# BOTTOM_BRD_v_1_0_3.net
KiCad netlist of a schematic drawn in EAGLE
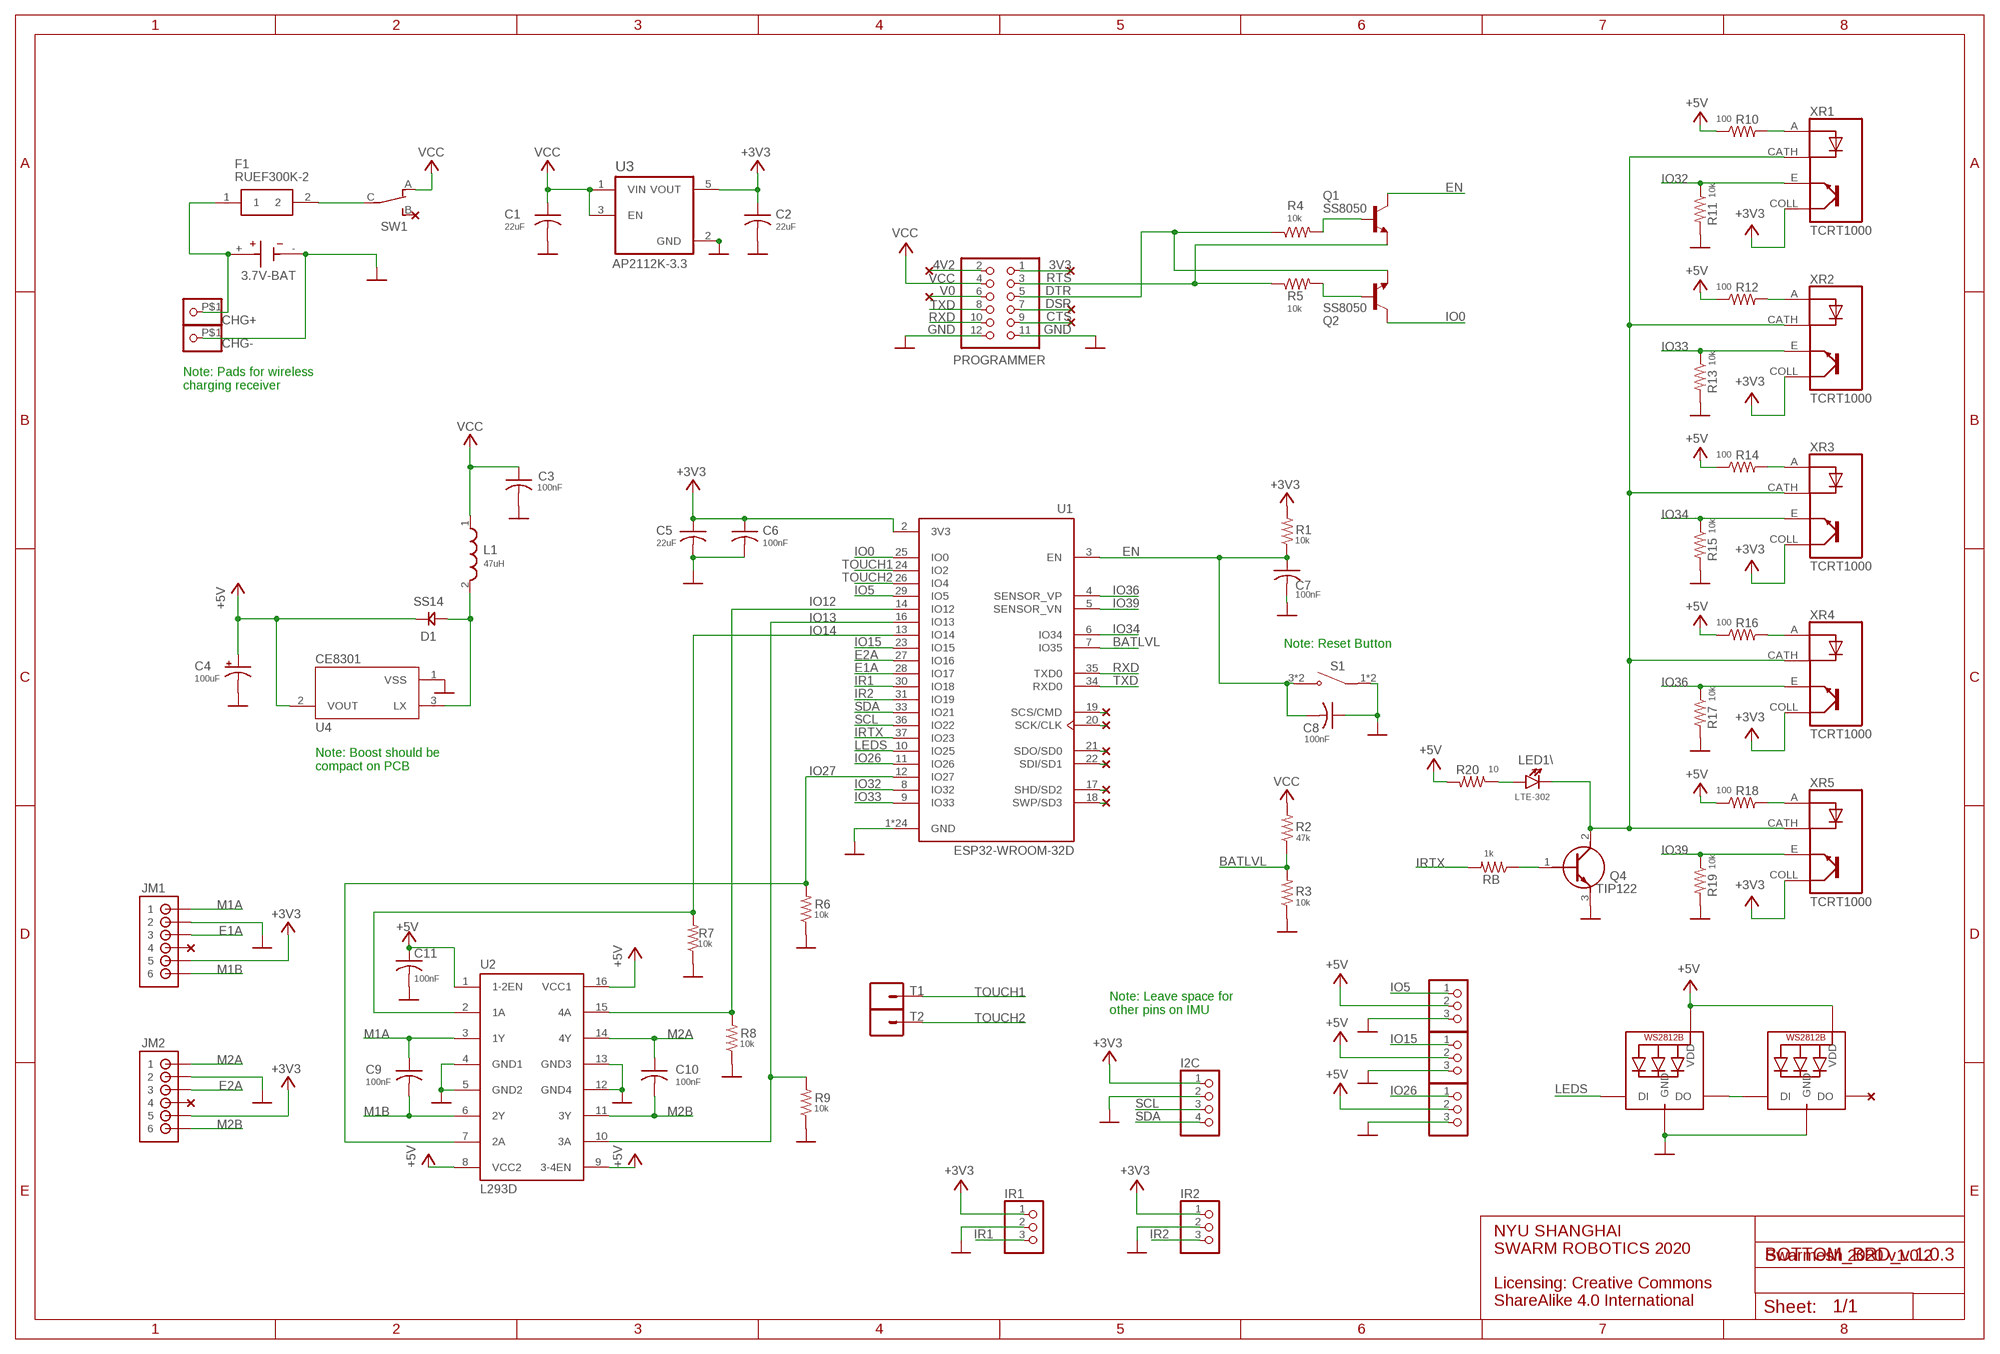
[diagram p0: schematic, sheet 1]

(export (version "E")
  (design (tool "Eeschema 10.0.6"))
  (components
    (comp (ref "BT")
      (value "3.7V-BAT")
      (footprint "eagle-import:BAT_6S-AA")
      (fields (field (name "MF") "MPD") (field (name "MP") "6S-AA"))
      (libsource (lib "eagle-import") (part "6S-AA"))
    )
    (comp (ref "C1")
      (value "22uF")
      (footprint "eagle-import:C0805")
      (libsource (lib "eagle-import") (part "C-USC0805"))
    )
    (comp (ref "C2")
      (value "22uF")
      (footprint "eagle-import:C0805")
      (libsource (lib "eagle-import") (part "C-USC0805"))
    )
    (comp (ref "C3")
      (value "100nF")
      (footprint "eagle-import:C0805")
      (libsource (lib "eagle-import") (part "C-USC0805"))
    )
    (comp (ref "C4")
      (value "100uF")
      (footprint "eagle-import:153CLV-0605")
      (libsource (lib "eagle-import") (part "CPOL-US153CLV-0605"))
    )
    (comp (ref "C5")
      (value "22uF")
      (footprint "eagle-import:C0805")
      (libsource (lib "eagle-import") (part "C-USC0805"))
    )
    (comp (ref "C6")
      (value "100nF")
      (footprint "eagle-import:C0805")
      (libsource (lib "eagle-import") (part "C-USC0805"))
    )
    (comp (ref "C7")
      (value "100nF")
      (footprint "eagle-import:C0805")
      (libsource (lib "eagle-import") (part "C-USC0805"))
    )
    (comp (ref "C8")
      (value "100nF")
      (footprint "eagle-import:C0805")
      (libsource (lib "eagle-import") (part "C-USC0805"))
    )
    (comp (ref "C9")
      (value "100nF")
      (footprint "eagle-import:C0805")
      (libsource (lib "eagle-import") (part "C-USC0805"))
    )
    (comp (ref "C10")
      (value "100nF")
      (footprint "eagle-import:C0805")
      (libsource (lib "eagle-import") (part "C-USC0805"))
    )
    (comp (ref "C11")
      (value "100nF")
      (footprint "eagle-import:C0805")
      (libsource (lib "eagle-import") (part "C-USC0805"))
    )
    (comp (ref "CHARGING")
      (value "WS2812B5050")
      (footprint "eagle-import:WS2812B")
      (libsource (lib "eagle-import") (part "WS2812B5050"))
    )
    (comp (ref "CHG+")
      (value "PINHD-1X1-BIGPOGO")
      (footprint "eagle-import:1X1-BIGPOGO")
      (libsource (lib "eagle-import") (part "PINHD-1X1-BIGPOGO"))
    )
    (comp (ref "CHG-")
      (value "PINHD-1X1-BIGPOGO")
      (footprint "eagle-import:1X1-BIGPOGO")
      (libsource (lib "eagle-import") (part "PINHD-1X1-BIGPOGO"))
    )
    (comp (ref "D1")
      (value "SS14")
      (footprint "eagle-import:DO214")
      (fields (field (name "MF") "ON Semiconductor"))
      (libsource (lib "eagle-import") (part "SS14"))
    )
    (comp (ref "F1")
      (value "RUEF300K-2")
      (footprint "eagle-import:RUEF300K2")
      (libsource (lib "eagle-import") (part "RUEF300K-2"))
    )
    (comp (ref "GPIO5")
      (value "PINHD-1X3")
      (footprint "eagle-import:1X03")
      (libsource (lib "eagle-import") (part "PINHD-1X3"))
    )
    (comp (ref "GPIO15")
      (value "PINHD-1X3")
      (footprint "eagle-import:1X03")
      (libsource (lib "eagle-import") (part "PINHD-1X3"))
    )
    (comp (ref "GPIO26")
      (value "PINHD-1X3")
      (footprint "eagle-import:1X03")
      (libsource (lib "eagle-import") (part "PINHD-1X3"))
    )
    (comp (ref "I2C")
      (value "PINHD-1X4")
      (footprint "eagle-import:1X04")
      (libsource (lib "eagle-import") (part "PINHD-1X4"))
    )
    (comp (ref "IR1")
      (value "PINHD-1X3")
      (footprint "eagle-import:1X03")
      (libsource (lib "eagle-import") (part "PINHD-1X3"))
    )
    (comp (ref "IR2")
      (value "PINHD-1X3")
      (footprint "eagle-import:1X03")
      (libsource (lib "eagle-import") (part "PINHD-1X3"))
    )
    (comp (ref "JM1")
      (value "B6B-ZR")
      (footprint "eagle-import:B6B-ZR")
      (fields (field (name "MF") "JST"))
      (libsource (lib "eagle-import") (part "B6B-ZR"))
    )
    (comp (ref "JM2")
      (value "B6B-ZR")
      (footprint "eagle-import:B6B-ZR")
      (fields (field (name "MF") "JST"))
      (libsource (lib "eagle-import") (part "B6B-ZR"))
    )
    (comp (ref "L1")
      (value "47uH")
      (footprint "eagle-import:INDP5858X480N")
      (fields (field (name "MF") "Bourns") (field (name "MP") "SDR0604-100KL"))
      (libsource (lib "eagle-import") (part "SDR0604-100KL"))
    )
    (comp (ref "LED1\\")
      (value "LTE-302")
      (footprint "eagle-import:LTE-302")
      (fields (field (name "DIGI-KEY_PART_NUMBER") "160-1930-ND") (field (name "MF") "Lite-On Inc."))
      (libsource (lib "eagle-import") (part "LTE-302"))
    )
    (comp (ref "PROGRAMMER")
      (value "PINHD-2X6")
      (footprint "eagle-import:2X06")
      (libsource (lib "eagle-import") (part "PINHD-2X6"))
    )
    (comp (ref "Q1")
      (value "SS8050")
      (footprint "eagle-import:SOT23")
      (libsource (lib "eagle-import") (part "BC850"))
    )
    (comp (ref "Q2")
      (value "SS8050")
      (footprint "eagle-import:SOT23")
      (libsource (lib "eagle-import") (part "BC850"))
    )
    (comp (ref "Q4")
      (value "TIP122")
      (footprint "eagle-import:TO270P460X1020X2008-3P")
      (fields (field (name "MOUSER_PART_NUMBER") "511-TIP122"))
      (libsource (lib "eagle-import") (part "TIP122"))
    )
    (comp (ref "R1")
      (value "10k")
      (footprint "eagle-import:M0805")
      (libsource (lib "eagle-import") (part "R-US_M0805"))
    )
    (comp (ref "R2")
      (value "47k")
      (footprint "eagle-import:M0805")
      (libsource (lib "eagle-import") (part "R-US_M0805"))
    )
    (comp (ref "R3")
      (value "10k")
      (footprint "eagle-import:M0805")
      (libsource (lib "eagle-import") (part "R-US_M0805"))
    )
    (comp (ref "R4")
      (value "10k")
      (footprint "eagle-import:M0805")
      (libsource (lib "eagle-import") (part "R-US_M0805"))
    )
    (comp (ref "R5")
      (value "10k")
      (footprint "eagle-import:M0805")
      (libsource (lib "eagle-import") (part "R-US_M0805"))
    )
    (comp (ref "R6")
      (value "10k")
      (footprint "eagle-import:M0805")
      (libsource (lib "eagle-import") (part "R-US_M0805"))
    )
    (comp (ref "R7")
      (value "10k")
      (footprint "eagle-import:M0805")
      (libsource (lib "eagle-import") (part "R-US_M0805"))
    )
    (comp (ref "R8")
      (value "10k")
      (footprint "eagle-import:M0805")
      (libsource (lib "eagle-import") (part "R-US_M0805"))
    )
    (comp (ref "R9")
      (value "10k")
      (footprint "eagle-import:M0805")
      (libsource (lib "eagle-import") (part "R-US_M0805"))
    )
    (comp (ref "R10")
      (value "100")
      (footprint "eagle-import:M0805")
      (libsource (lib "eagle-import") (part "R-US_M0805"))
    )
    (comp (ref "R11")
      (value "10k")
      (footprint "eagle-import:M0805")
      (libsource (lib "eagle-import") (part "R-US_M0805"))
    )
    (comp (ref "R12")
      (value "100")
      (footprint "eagle-import:M0805")
      (libsource (lib "eagle-import") (part "R-US_M0805"))
    )
    (comp (ref "R13")
      (value "10k")
      (footprint "eagle-import:M0805")
      (libsource (lib "eagle-import") (part "R-US_M0805"))
    )
    (comp (ref "R14")
      (value "100")
      (footprint "eagle-import:M0805")
      (libsource (lib "eagle-import") (part "R-US_M0805"))
    )
    (comp (ref "R15")
      (value "10k")
      (footprint "eagle-import:M0805")
      (libsource (lib "eagle-import") (part "R-US_M0805"))
    )
    (comp (ref "R16")
      (value "100")
      (footprint "eagle-import:M0805")
      (libsource (lib "eagle-import") (part "R-US_M0805"))
    )
    (comp (ref "R17")
      (value "10k")
      (footprint "eagle-import:M0805")
      (libsource (lib "eagle-import") (part "R-US_M0805"))
    )
    (comp (ref "R18")
      (value "100")
      (footprint "eagle-import:M0805")
      (libsource (lib "eagle-import") (part "R-US_M0805"))
    )
    (comp (ref "R19")
      (value "10k")
      (footprint "eagle-import:M0805")
      (libsource (lib "eagle-import") (part "R-US_M0805"))
    )
    (comp (ref "R20")
      (value "10")
      (footprint "eagle-import:M0805")
      (libsource (lib "eagle-import") (part "R-US_M0805"))
    )
    (comp (ref "RB")
      (value "1k")
      (footprint "eagle-import:M0805")
      (libsource (lib "eagle-import") (part "R-US_M0805"))
    )
    (comp (ref "S1")
      (value "2-1437565-9")
      (footprint "eagle-import:SW_2-1437565-9")
      (fields (field (name "MF") "TE Connectivity"))
      (libsource (lib "eagle-import") (part "2-1437565-9"))
    )
    (comp (ref "STATE")
      (value "WS2812B5050")
      (footprint "eagle-import:WS2812B")
      (libsource (lib "eagle-import") (part "WS2812B5050"))
    )
    (comp (ref "SW1")
      (value "CS12ANW03")
      (footprint "eagle-import:CS12ANW03")
      (fields (field (name "MF") "NKK Switches"))
      (libsource (lib "eagle-import") (part "CS12ANW03"))
    )
    (comp (ref "T1")
      (value "CONN_01SPRING-CONN")
      (footprint "eagle-import:SPRING-CONNECTOR")
      (libsource (lib "eagle-import") (part "CONN_01SPRING-CONN"))
    )
    (comp (ref "T2")
      (value "CONN_01SPRING-CONN")
      (footprint "eagle-import:SPRING-CONNECTOR")
      (libsource (lib "eagle-import") (part "CONN_01SPRING-CONN"))
    )
    (comp (ref "U1")
      (value "ESP32-WROOM-32D")
      (footprint "eagle-import:MODULE_ESP32-WROOM-32D")
      (fields (field (name "MF") "Espressif Systems"))
      (libsource (lib "eagle-import") (part "ESP32-WROOM-32D"))
    )
    (comp (ref "U2")
      (value "L293D")
      (footprint "eagle-import:DIL16")
      (libsource (lib "eagle-import") (part "L293D"))
    )
    (comp (ref "U3")
      (value "AP2112K-3.3")
      (footprint "eagle-import:SOT95P285X140-5N")
      (fields (field (name "MF") "Diodes Inc.") (field (name "MP") "AP2112K-3.3TRG1"))
      (libsource (lib "eagle-import") (part "AP2112K-3.3TRG1"))
    )
    (comp (ref "U4")
      (value "CE8301")
      (footprint "eagle-import:REG_MCP1702T-3302E_MB")
      (fields (field (name "MF") "Microchip") (field (name "MP") "MCP1702T-3302E/MB"))
      (libsource (lib "eagle-import") (part "MCP1702T-3302E/MB"))
    )
    (comp (ref "XR1")
      (value "TCRT1000")
      (footprint "eagle-import:XDCR_TCRT1000")
      (fields (field (name "MF") "Vishay"))
      (libsource (lib "eagle-import") (part "TCRT1000"))
    )
    (comp (ref "XR2")
      (value "TCRT1000")
      (footprint "eagle-import:XDCR_TCRT1000")
      (fields (field (name "MF") "Vishay"))
      (libsource (lib "eagle-import") (part "TCRT1000"))
    )
    (comp (ref "XR3")
      (value "TCRT1000")
      (footprint "eagle-import:XDCR_TCRT1000")
      (fields (field (name "MF") "Vishay"))
      (libsource (lib "eagle-import") (part "TCRT1000"))
    )
    (comp (ref "XR4")
      (value "TCRT1000")
      (footprint "eagle-import:XDCR_TCRT1000")
      (fields (field (name "MF") "Vishay"))
      (libsource (lib "eagle-import") (part "TCRT1000"))
    )
    (comp (ref "XR5")
      (value "TCRT1000")
      (footprint "eagle-import:XDCR_TCRT1000")
      (fields (field (name "MF") "Vishay"))
      (libsource (lib "eagle-import") (part "TCRT1000"))
    )
  )
  (nets
    (net (code "1") (name "+3V3") (class "Default")
      (node (ref "C2") (pin "1") (pinfunction "1_1") (pintype "passive"))
      (node (ref "C5") (pin "1") (pinfunction "1_1") (pintype "passive"))
      (node (ref "C6") (pin "1") (pinfunction "1_1") (pintype "passive"))
      (node (ref "I2C") (pin "1") (pinfunction "1_1") (pintype "passive"))
      (node (ref "IR1") (pin "1") (pinfunction "1_1") (pintype "passive"))
      (node (ref "IR2") (pin "1") (pinfunction "1_1") (pintype "passive"))
      (node (ref "JM1") (pin "5") (pinfunction "5_5") (pintype "bidirectional"))
      (node (ref "JM2") (pin "5") (pinfunction "5_5") (pintype "bidirectional"))
      (node (ref "R1") (pin "2") (pinfunction "2_2") (pintype "passive"))
      (node (ref "U1") (pin "2") (pinfunction "3V3_2") (pintype "power_in"))
      (node (ref "U3") (pin "5") (pinfunction "VOUT_5") (pintype "power_in"))
      (node (ref "XR1") (pin "COLL") (pinfunction "CO_COLL") (pintype "passive"))
      (node (ref "XR2") (pin "COLL") (pinfunction "CO_COLL") (pintype "passive"))
      (node (ref "XR3") (pin "COLL") (pinfunction "CO_COLL") (pintype "passive"))
      (node (ref "XR4") (pin "COLL") (pinfunction "CO_COLL") (pintype "passive"))
      (node (ref "XR5") (pin "COLL") (pinfunction "CO_COLL") (pintype "passive"))
    )
    (net (code "2") (name "+5V") (class "Default")
      (node (ref "C11") (pin "1") (pinfunction "1_1") (pintype "passive"))
      (node (ref "C4") (pin "+") (pinfunction "+_+") (pintype "passive"))
      (node (ref "CHARGING") (pin "1-VDD") (pinfunction "VDD_1-VDD") (pintype "power_in"))
      (node (ref "D1") (pin "CATHODE") (pinfunction "KATHODE_CATHODE") (pintype "bidirectional"))
      (node (ref "GPIO15") (pin "2") (pinfunction "2_2") (pintype "passive"))
      (node (ref "GPIO26") (pin "2") (pinfunction "2_2") (pintype "passive"))
      (node (ref "GPIO5") (pin "2") (pinfunction "2_2") (pintype "passive"))
      (node (ref "R10") (pin "1") (pinfunction "1_1") (pintype "passive"))
      (node (ref "R12") (pin "1") (pinfunction "1_1") (pintype "passive"))
      (node (ref "R14") (pin "1") (pinfunction "1_1") (pintype "passive"))
      (node (ref "R16") (pin "1") (pinfunction "1_1") (pintype "passive"))
      (node (ref "R18") (pin "1") (pinfunction "1_1") (pintype "passive"))
      (node (ref "R20") (pin "2") (pinfunction "2_2") (pintype "passive"))
      (node (ref "STATE") (pin "1-VDD") (pinfunction "VDD_1-VDD") (pintype "power_in"))
      (node (ref "U2") (pin "1") (pinfunction "1-2EN_1") (pintype "input"))
      (node (ref "U2") (pin "16") (pinfunction "VCC1_16") (pintype "power_in"))
      (node (ref "U2") (pin "8") (pinfunction "VCC2_8") (pintype "power_in"))
      (node (ref "U2") (pin "9") (pinfunction "3-4EN_9") (pintype "input"))
      (node (ref "U4") (pin "2") (pinfunction "VOUT_2") (pintype "input"))
    )
    (net (code "3") (name "/3V3") (class "Default")
      (node (ref "PROGRAMMER") (pin "1") (pinfunction "1_1") (pintype "passive"))
    )
    (net (code "4") (name "/4V2") (class "Default")
      (node (ref "PROGRAMMER") (pin "2") (pinfunction "2_2") (pintype "passive"))
    )
    (net (code "5") (name "/BATLVL") (class "Default")
      (node (ref "R2") (pin "1") (pinfunction "1_1") (pintype "passive"))
      (node (ref "R3") (pin "2") (pinfunction "2_2") (pintype "passive"))
      (node (ref "U1") (pin "7") (pinfunction "IO35_7") (pintype "input"))
    )
    (net (code "6") (name "/CTS") (class "Default")
      (node (ref "PROGRAMMER") (pin "9") (pinfunction "9_9") (pintype "passive"))
    )
    (net (code "7") (name "/DSR") (class "Default")
      (node (ref "PROGRAMMER") (pin "7") (pinfunction "7_7") (pintype "passive"))
    )
    (net (code "8") (name "/DTR") (class "Default")
      (node (ref "PROGRAMMER") (pin "5") (pinfunction "5_5") (pintype "passive"))
      (node (ref "Q2") (pin "2") (pinfunction "E_2") (pintype "passive"))
      (node (ref "R4") (pin "1") (pinfunction "1_1") (pintype "passive"))
    )
    (net (code "9") (name "/E1A") (class "Default")
      (node (ref "JM1") (pin "3") (pinfunction "3_3") (pintype "bidirectional"))
      (node (ref "U1") (pin "28") (pinfunction "IO17_28") (pintype "bidirectional"))
    )
    (net (code "10") (name "/E2A") (class "Default")
      (node (ref "JM2") (pin "3") (pinfunction "3_3") (pintype "bidirectional"))
      (node (ref "U1") (pin "27") (pinfunction "IO16_27") (pintype "bidirectional"))
    )
    (net (code "11") (name "/EN") (class "Default")
      (node (ref "C7") (pin "1") (pinfunction "1_1") (pintype "passive"))
      (node (ref "C8") (pin "2") (pinfunction "2_2") (pintype "passive"))
      (node (ref "Q1") (pin "3") (pinfunction "C_3") (pintype "passive"))
      (node (ref "R1") (pin "1") (pinfunction "1_1") (pintype "passive"))
      (node (ref "S1") (pin "3") (pinfunction "NO_3") (pintype "passive"))
      (node (ref "S1") (pin "4") (pinfunction "NO_4") (pintype "passive"))
      (node (ref "U1") (pin "3") (pinfunction "EN_3") (pintype "input"))
    )
    (net (code "12") (name "/IO0") (class "Default")
      (node (ref "Q2") (pin "3") (pinfunction "C_3") (pintype "passive"))
      (node (ref "U1") (pin "25") (pinfunction "IO0_25") (pintype "bidirectional"))
    )
    (net (code "13") (name "/IO5") (class "Default")
      (node (ref "GPIO5") (pin "1") (pinfunction "1_1") (pintype "passive"))
      (node (ref "U1") (pin "29") (pinfunction "IO5_29") (pintype "bidirectional"))
    )
    (net (code "14") (name "/IO12") (class "Default")
      (node (ref "R8") (pin "2") (pinfunction "2_2") (pintype "passive"))
      (node (ref "U1") (pin "14") (pinfunction "IO12_14") (pintype "bidirectional"))
      (node (ref "U2") (pin "15") (pinfunction "4A_15") (pintype "input"))
    )
    (net (code "15") (name "/IO13") (class "Default")
      (node (ref "R9") (pin "2") (pinfunction "2_2") (pintype "passive"))
      (node (ref "U1") (pin "16") (pinfunction "IO13_16") (pintype "bidirectional"))
      (node (ref "U2") (pin "10") (pinfunction "3A_10") (pintype "input"))
    )
    (net (code "16") (name "/IO14") (class "Default")
      (node (ref "R7") (pin "2") (pinfunction "2_2") (pintype "passive"))
      (node (ref "U1") (pin "13") (pinfunction "IO14_13") (pintype "bidirectional"))
      (node (ref "U2") (pin "2") (pinfunction "1A_2") (pintype "input"))
    )
    (net (code "17") (name "/IO15") (class "Default")
      (node (ref "GPIO15") (pin "1") (pinfunction "1_1") (pintype "passive"))
      (node (ref "U1") (pin "23") (pinfunction "IO15_23") (pintype "bidirectional"))
    )
    (net (code "18") (name "/IO26") (class "Default")
      (node (ref "GPIO26") (pin "1") (pinfunction "1_1") (pintype "passive"))
      (node (ref "U1") (pin "11") (pinfunction "IO26_11") (pintype "bidirectional"))
    )
    (net (code "19") (name "/IO27") (class "Default")
      (node (ref "R6") (pin "2") (pinfunction "2_2") (pintype "passive"))
      (node (ref "U1") (pin "12") (pinfunction "IO27_12") (pintype "bidirectional"))
      (node (ref "U2") (pin "7") (pinfunction "2A_7") (pintype "input"))
    )
    (net (code "20") (name "/IO32") (class "Default")
      (node (ref "R11") (pin "1") (pinfunction "1_1") (pintype "passive"))
      (node (ref "U1") (pin "8") (pinfunction "IO32_8") (pintype "bidirectional"))
      (node (ref "XR1") (pin "E") (pinfunction "E_E") (pintype "passive"))
    )
    (net (code "21") (name "/IO33") (class "Default")
      (node (ref "R13") (pin "1") (pinfunction "1_1") (pintype "passive"))
      (node (ref "U1") (pin "9") (pinfunction "IO33_9") (pintype "bidirectional"))
      (node (ref "XR2") (pin "E") (pinfunction "E_E") (pintype "passive"))
    )
    (net (code "22") (name "/IO34") (class "Default")
      (node (ref "R15") (pin "1") (pinfunction "1_1") (pintype "passive"))
      (node (ref "U1") (pin "6") (pinfunction "IO34_6") (pintype "input"))
      (node (ref "XR3") (pin "E") (pinfunction "E_E") (pintype "passive"))
    )
    (net (code "23") (name "/IO36") (class "Default")
      (node (ref "R17") (pin "1") (pinfunction "1_1") (pintype "passive"))
      (node (ref "U1") (pin "4") (pinfunction "SENSOR_VP_4") (pintype "input"))
      (node (ref "XR4") (pin "E") (pinfunction "E_E") (pintype "passive"))
    )
    (net (code "24") (name "/IO39") (class "Default")
      (node (ref "R19") (pin "1") (pinfunction "1_1") (pintype "passive"))
      (node (ref "U1") (pin "5") (pinfunction "SENSOR_VN_5") (pintype "input"))
      (node (ref "XR5") (pin "E") (pinfunction "E_E") (pintype "passive"))
    )
    (net (code "25") (name "/IR1") (class "Default")
      (node (ref "IR1") (pin "3") (pinfunction "3_3") (pintype "passive"))
      (node (ref "U1") (pin "30") (pinfunction "IO18_30") (pintype "bidirectional"))
    )
    (net (code "26") (name "/IR2") (class "Default")
      (node (ref "IR2") (pin "3") (pinfunction "3_3") (pintype "passive"))
      (node (ref "U1") (pin "31") (pinfunction "IO19_31") (pintype "bidirectional"))
    )
    (net (code "27") (name "/IRTX") (class "Default")
      (node (ref "RB") (pin "2") (pinfunction "2_2") (pintype "passive"))
      (node (ref "U1") (pin "37") (pinfunction "IO23_37") (pintype "bidirectional"))
    )
    (net (code "28") (name "/LEDS") (class "Default")
      (node (ref "CHARGING") (pin "4-DIN") (pinfunction "DI_4-DIN") (pintype "input"))
      (node (ref "U1") (pin "10") (pinfunction "IO25_10") (pintype "bidirectional"))
    )
    (net (code "29") (name "/M1A") (class "Default")
      (node (ref "C9") (pin "1") (pinfunction "1_1") (pintype "passive"))
      (node (ref "JM1") (pin "1") (pinfunction "1_1") (pintype "bidirectional"))
      (node (ref "U2") (pin "3") (pinfunction "1Y_3") (pintype "output"))
    )
    (net (code "30") (name "/M1B") (class "Default")
      (node (ref "C9") (pin "2") (pinfunction "2_2") (pintype "passive"))
      (node (ref "JM1") (pin "6") (pinfunction "6_6") (pintype "bidirectional"))
      (node (ref "U2") (pin "6") (pinfunction "2Y_6") (pintype "output"))
    )
    (net (code "31") (name "/M2A") (class "Default")
      (node (ref "C10") (pin "1") (pinfunction "1_1") (pintype "passive"))
      (node (ref "JM2") (pin "1") (pinfunction "1_1") (pintype "bidirectional"))
      (node (ref "U2") (pin "14") (pinfunction "4Y_14") (pintype "output"))
    )
    (net (code "32") (name "/M2B") (class "Default")
      (node (ref "C10") (pin "2") (pinfunction "2_2") (pintype "passive"))
      (node (ref "JM2") (pin "6") (pinfunction "6_6") (pintype "bidirectional"))
      (node (ref "U2") (pin "11") (pinfunction "3Y_11") (pintype "output"))
    )
    (net (code "33") (name "/RTS") (class "Default")
      (node (ref "PROGRAMMER") (pin "3") (pinfunction "3_3") (pintype "passive"))
      (node (ref "Q1") (pin "2") (pinfunction "E_2") (pintype "passive"))
      (node (ref "R5") (pin "1") (pinfunction "1_1") (pintype "passive"))
    )
    (net (code "34") (name "/RXD") (class "Default")
      (node (ref "PROGRAMMER") (pin "10") (pinfunction "10_10") (pintype "passive"))
      (node (ref "U1") (pin "35") (pinfunction "TXD0_35") (pintype "bidirectional"))
    )
    (net (code "35") (name "/SCL") (class "Default")
      (node (ref "I2C") (pin "3") (pinfunction "3_3") (pintype "passive"))
      (node (ref "U1") (pin "36") (pinfunction "IO22_36") (pintype "bidirectional"))
    )
    (net (code "36") (name "/SDA") (class "Default")
      (node (ref "I2C") (pin "4") (pinfunction "4_4") (pintype "passive"))
      (node (ref "U1") (pin "33") (pinfunction "IO21_33") (pintype "bidirectional"))
    )
    (net (code "37") (name "/TOUCH1") (class "Default")
      (node (ref "T1") (pin "P$2") (pinfunction "1_P$2") (pintype "passive"))
      (node (ref "U1") (pin "24") (pinfunction "IO2_24") (pintype "bidirectional"))
    )
    (net (code "38") (name "/TOUCH2") (class "Default")
      (node (ref "T2") (pin "P$2") (pinfunction "1_P$2") (pintype "passive"))
      (node (ref "U1") (pin "26") (pinfunction "IO4_26") (pintype "bidirectional"))
    )
    (net (code "39") (name "/TXD") (class "Default")
      (node (ref "PROGRAMMER") (pin "8") (pinfunction "8_8") (pintype "passive"))
      (node (ref "U1") (pin "34") (pinfunction "RXD0_34") (pintype "bidirectional"))
    )
    (net (code "40") (name "/V0") (class "Default")
      (node (ref "PROGRAMMER") (pin "6") (pinfunction "6_6") (pintype "passive"))
    )
    (net (code "41") (name "GND") (class "Default")
      (node (ref "BT") (pin "-") (pinfunction "-_-") (pintype "passive"))
      (node (ref "C1") (pin "2") (pinfunction "2_2") (pintype "passive"))
      (node (ref "C11") (pin "2") (pinfunction "2_2") (pintype "passive"))
      (node (ref "C2") (pin "2") (pinfunction "2_2") (pintype "passive"))
      (node (ref "C3") (pin "2") (pinfunction "2_2") (pintype "passive"))
      (node (ref "C4") (pin "-") (pinfunction "-_-") (pintype "passive"))
      (node (ref "C5") (pin "2") (pinfunction "2_2") (pintype "passive"))
      (node (ref "C6") (pin "2") (pinfunction "2_2") (pintype "passive"))
      (node (ref "C7") (pin "2") (pinfunction "2_2") (pintype "passive"))
      (node (ref "C8") (pin "1") (pinfunction "1_1") (pintype "passive"))
      (node (ref "CHARGING") (pin "3-GND") (pinfunction "GND_3-GND") (pintype "power_in"))
      (node (ref "CHG-") (pin "P$1") (pinfunction "1_P$1") (pintype "passive"))
      (node (ref "GPIO15") (pin "3") (pinfunction "3_3") (pintype "passive"))
      (node (ref "GPIO26") (pin "3") (pinfunction "3_3") (pintype "passive"))
      (node (ref "GPIO5") (pin "3") (pinfunction "3_3") (pintype "passive"))
      (node (ref "I2C") (pin "2") (pinfunction "2_2") (pintype "passive"))
      (node (ref "IR1") (pin "2") (pinfunction "2_2") (pintype "passive"))
      (node (ref "IR2") (pin "2") (pinfunction "2_2") (pintype "passive"))
      (node (ref "JM1") (pin "2") (pinfunction "2_2") (pintype "bidirectional"))
      (node (ref "JM2") (pin "2") (pinfunction "2_2") (pintype "bidirectional"))
      (node (ref "PROGRAMMER") (pin "11") (pinfunction "11_11") (pintype "passive"))
      (node (ref "PROGRAMMER") (pin "12") (pinfunction "12_12") (pintype "passive"))
      (node (ref "Q4") (pin "3") (pinfunction "E_3") (pintype "bidirectional"))
      (node (ref "R11") (pin "2") (pinfunction "2_2") (pintype "passive"))
      (node (ref "R13") (pin "2") (pinfunction "2_2") (pintype "passive"))
      (node (ref "R15") (pin "2") (pinfunction "2_2") (pintype "passive"))
      (node (ref "R17") (pin "2") (pinfunction "2_2") (pintype "passive"))
      (node (ref "R19") (pin "2") (pinfunction "2_2") (pintype "passive"))
      (node (ref "R3") (pin "1") (pinfunction "1_1") (pintype "passive"))
      (node (ref "R6") (pin "1") (pinfunction "1_1") (pintype "passive"))
      (node (ref "R7") (pin "1") (pinfunction "1_1") (pintype "passive"))
      (node (ref "R8") (pin "1") (pinfunction "1_1") (pintype "passive"))
      (node (ref "R9") (pin "1") (pinfunction "1_1") (pintype "passive"))
      (node (ref "S1") (pin "1") (pinfunction "COM_1") (pintype "passive"))
      (node (ref "S1") (pin "2") (pinfunction "COM_2") (pintype "passive"))
      (node (ref "STATE") (pin "3-GND") (pinfunction "GND_3-GND") (pintype "power_in"))
      (node (ref "U1") (pin "1") (pinfunction "GND_1") (pintype "power_in"))
      (node (ref "U1") (pin "15") (pinfunction "GND_15") (pintype "power_in"))
      (node (ref "U1") (pin "38") (pinfunction "GND_38") (pintype "power_in"))
      (node (ref "U1") (pin "39_1") (pinfunction "GND_39_1") (pintype "power_in"))
      (node (ref "U1") (pin "39_10") (pinfunction "GND_39_10") (pintype "power_in"))
      (node (ref "U1") (pin "39_11") (pinfunction "GND_39_11") (pintype "power_in"))
      (node (ref "U1") (pin "39_12") (pinfunction "GND_39_12") (pintype "power_in"))
      (node (ref "U1") (pin "39_13") (pinfunction "GND_39_13") (pintype "power_in"))
      (node (ref "U1") (pin "39_14") (pinfunction "GND_39_14") (pintype "power_in"))
      (node (ref "U1") (pin "39_15") (pinfunction "GND_39_15") (pintype "power_in"))
      (node (ref "U1") (pin "39_16") (pinfunction "GND_39_16") (pintype "power_in"))
      (node (ref "U1") (pin "39_17") (pinfunction "GND_39_17") (pintype "power_in"))
      (node (ref "U1") (pin "39_18") (pinfunction "GND_39_18") (pintype "power_in"))
      (node (ref "U1") (pin "39_19") (pinfunction "GND_39_19") (pintype "power_in"))
      (node (ref "U1") (pin "39_2") (pinfunction "GND_39_2") (pintype "power_in"))
      (node (ref "U1") (pin "39_20") (pinfunction "GND_39_20") (pintype "power_in"))
      (node (ref "U1") (pin "39_21") (pinfunction "GND_39_21") (pintype "power_in"))
      (node (ref "U1") (pin "39_3") (pinfunction "GND_39_3") (pintype "power_in"))
      (node (ref "U1") (pin "39_4") (pinfunction "GND_39_4") (pintype "power_in"))
      (node (ref "U1") (pin "39_5") (pinfunction "GND_39_5") (pintype "power_in"))
      (node (ref "U1") (pin "39_6") (pinfunction "GND_39_6") (pintype "power_in"))
      (node (ref "U1") (pin "39_7") (pinfunction "GND_39_7") (pintype "power_in"))
      (node (ref "U1") (pin "39_8") (pinfunction "GND_39_8") (pintype "power_in"))
      (node (ref "U1") (pin "39_9") (pinfunction "GND_39_9") (pintype "power_in"))
      (node (ref "U2") (pin "12") (pinfunction "GND4_12") (pintype "power_in"))
      (node (ref "U2") (pin "13") (pinfunction "GND3_13") (pintype "power_in"))
      (node (ref "U2") (pin "4") (pinfunction "GND1_4") (pintype "power_in"))
      (node (ref "U2") (pin "5") (pinfunction "GND2_5") (pintype "power_in"))
      (node (ref "U3") (pin "2") (pinfunction "GND_2") (pintype "power_in"))
      (node (ref "U4") (pin "1") (pinfunction "VSS_1") (pintype "power_in"))
    )
    (net (code "42") (name "Net-(CHARGING-DO)") (class "Default")
      (node (ref "CHARGING") (pin "2-DOUT") (pinfunction "DO_2-DOUT") (pintype "output"))
      (node (ref "STATE") (pin "4-DIN") (pinfunction "DI_4-DIN") (pintype "input"))
    )
    (net (code "43") (name "Net-(CHG+-1)") (class "Default")
      (node (ref "BT") (pin "+") (pinfunction "+_+") (pintype "passive"))
      (node (ref "CHG+") (pin "P$1") (pinfunction "1_P$1") (pintype "passive"))
      (node (ref "F1") (pin "1") (pinfunction "1_1") (pintype "bidirectional"))
    )
    (net (code "44") (name "Net-(F1-Pad2)") (class "Default")
      (node (ref "F1") (pin "2") (pinfunction "2_2") (pintype "bidirectional"))
      (node (ref "SW1") (pin "C") (pinfunction "C_C") (pintype "passive"))
    )
    (net (code "45") (name "Net-(LED1\\-PadA)") (class "Default")
      (node (ref "LED1\\") (pin "A") (pinfunction "A_A") (pintype "bidirectional"))
      (node (ref "R20") (pin "1") (pinfunction "1_1") (pintype "passive"))
    )
    (net (code "46") (name "Net-(Q1-B)") (class "Default")
      (node (ref "Q1") (pin "1") (pinfunction "B_1") (pintype "passive"))
      (node (ref "R4") (pin "2") (pinfunction "2_2") (pintype "passive"))
    )
    (net (code "47") (name "Net-(Q2-B)") (class "Default")
      (node (ref "Q2") (pin "1") (pinfunction "B_1") (pintype "passive"))
      (node (ref "R5") (pin "2") (pinfunction "2_2") (pintype "passive"))
    )
    (net (code "48") (name "Net-(Q4-B)") (class "Default")
      (node (ref "Q4") (pin "1") (pinfunction "B_1") (pintype "bidirectional"))
      (node (ref "RB") (pin "1") (pinfunction "1_1") (pintype "passive"))
    )
    (net (code "49") (name "Net-(Q4-C)") (class "Default")
      (node (ref "LED1\\") (pin "C") (pinfunction "C_C") (pintype "bidirectional"))
      (node (ref "Q4") (pin "2") (pinfunction "C_2") (pintype "bidirectional"))
      (node (ref "XR1") (pin "CATH") (pinfunction "C_CATH") (pintype "passive"))
      (node (ref "XR2") (pin "CATH") (pinfunction "C_CATH") (pintype "passive"))
      (node (ref "XR3") (pin "CATH") (pinfunction "C_CATH") (pintype "passive"))
      (node (ref "XR4") (pin "CATH") (pinfunction "C_CATH") (pintype "passive"))
      (node (ref "XR5") (pin "CATH") (pinfunction "C_CATH") (pintype "passive"))
    )
    (net (code "50") (name "Net-(R10-Pad2)") (class "Default")
      (node (ref "R10") (pin "2") (pinfunction "2_2") (pintype "passive"))
      (node (ref "XR1") (pin "A") (pinfunction "A_A") (pintype "passive"))
    )
    (net (code "51") (name "Net-(R12-Pad2)") (class "Default")
      (node (ref "R12") (pin "2") (pinfunction "2_2") (pintype "passive"))
      (node (ref "XR2") (pin "A") (pinfunction "A_A") (pintype "passive"))
    )
    (net (code "52") (name "Net-(R14-Pad2)") (class "Default")
      (node (ref "R14") (pin "2") (pinfunction "2_2") (pintype "passive"))
      (node (ref "XR3") (pin "A") (pinfunction "A_A") (pintype "passive"))
    )
    (net (code "53") (name "Net-(R16-Pad2)") (class "Default")
      (node (ref "R16") (pin "2") (pinfunction "2_2") (pintype "passive"))
      (node (ref "XR4") (pin "A") (pinfunction "A_A") (pintype "passive"))
    )
    (net (code "54") (name "Net-(R18-Pad2)") (class "Default")
      (node (ref "R18") (pin "2") (pinfunction "2_2") (pintype "passive"))
      (node (ref "XR5") (pin "A") (pinfunction "A_A") (pintype "passive"))
    )
    (net (code "55") (name "Net-(U4-LX)") (class "Default")
      (node (ref "D1") (pin "ANODE") (pinfunction "ANODE_ANODE") (pintype "bidirectional"))
      (node (ref "L1") (pin "2") (pinfunction "2_2") (pintype "passive"))
      (node (ref "U4") (pin "3") (pinfunction "LX_3") (pintype "output"))
    )
    (net (code "56") (name "VCC") (class "Default")
      (node (ref "C1") (pin "1") (pinfunction "1_1") (pintype "passive"))
      (node (ref "C3") (pin "1") (pinfunction "1_1") (pintype "passive"))
      (node (ref "L1") (pin "1") (pinfunction "1_1") (pintype "passive"))
      (node (ref "PROGRAMMER") (pin "4") (pinfunction "4_4") (pintype "passive"))
      (node (ref "R2") (pin "2") (pinfunction "2_2") (pintype "passive"))
      (node (ref "SW1") (pin "A") (pinfunction "A_A") (pintype "passive"))
      (node (ref "U3") (pin "1") (pinfunction "VIN_1") (pintype "power_in"))
      (node (ref "U3") (pin "3") (pinfunction "EN_3") (pintype "input"))
    )
    (net (code "57") (name "unconnected-(JM1-Pad4)") (class "Default")
      (node (ref "JM1") (pin "4") (pinfunction "4_4") (pintype "bidirectional"))
    )
    (net (code "58") (name "unconnected-(JM2-Pad4)") (class "Default")
      (node (ref "JM2") (pin "4") (pinfunction "4_4") (pintype "bidirectional"))
    )
    (net (code "59") (name "unconnected-(STATE-DO-Pad2-DOUT)") (class "Default")
      (node (ref "STATE") (pin "2-DOUT") (pinfunction "DO_2-DOUT") (pintype "output"))
    )
    (net (code "60") (name "unconnected-(SW1-PadB)") (class "Default")
      (node (ref "SW1") (pin "B") (pinfunction "B_B") (pintype "passive"))
    )
    (net (code "61") (name "unconnected-(U1-SCK{slash}CLK-Pad20)") (class "Default")
      (node (ref "U1") (pin "20") (pinfunction "SCK/CLK_20") (pintype "bidirectional"))
    )
    (net (code "62") (name "unconnected-(U1-SCS{slash}CMD-Pad19)") (class "Default")
      (node (ref "U1") (pin "19") (pinfunction "SCS/CMD_19") (pintype "bidirectional"))
    )
    (net (code "63") (name "unconnected-(U1-SDI{slash}SD1-Pad22)") (class "Default")
      (node (ref "U1") (pin "22") (pinfunction "SDI/SD1_22") (pintype "bidirectional"))
    )
    (net (code "64") (name "unconnected-(U1-SDO{slash}SD0-Pad21)") (class "Default")
      (node (ref "U1") (pin "21") (pinfunction "SDO/SD0_21") (pintype "bidirectional"))
    )
    (net (code "65") (name "unconnected-(U1-SHD{slash}SD2-Pad17)") (class "Default")
      (node (ref "U1") (pin "17") (pinfunction "SHD/SD2_17") (pintype "bidirectional"))
    )
    (net (code "66") (name "unconnected-(U1-SWP{slash}SD3-Pad18)") (class "Default")
      (node (ref "U1") (pin "18") (pinfunction "SWP/SD3_18") (pintype "bidirectional"))
    )
  )
)
